# Connector.net
KiCad netlist of a schematic drawn in Altium Designer
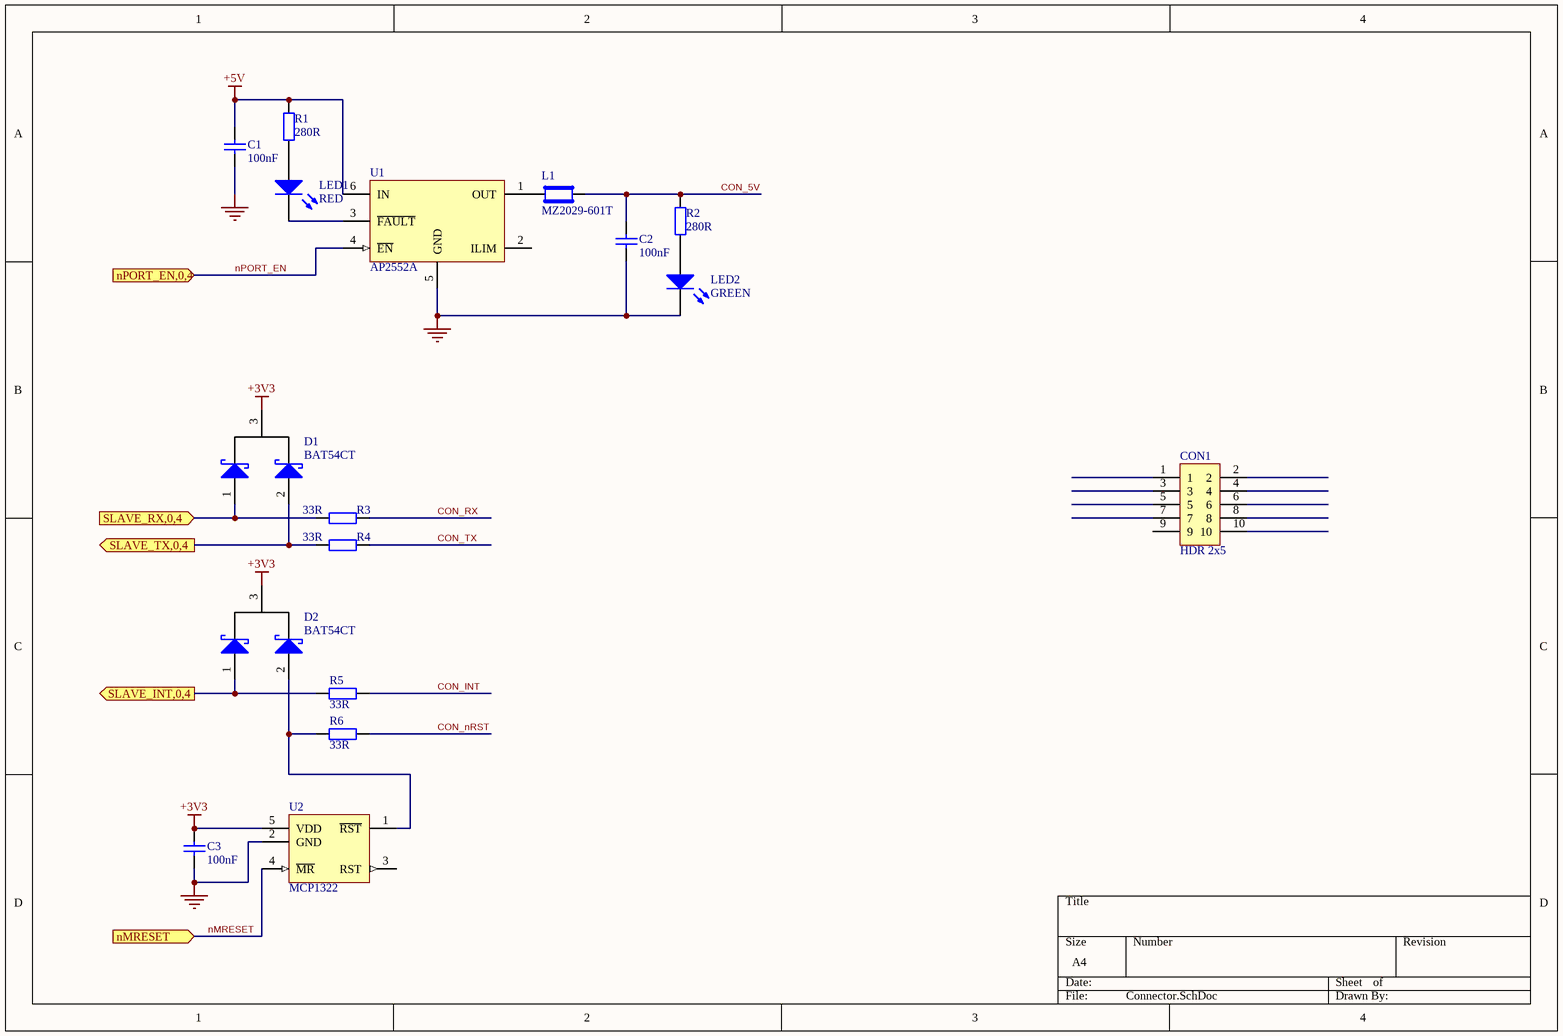
[diagram p0: Connector.SchDoc]

(export (version "E")
  (design (tool "Eeschema 10.0.6"))
  (components
    (comp (ref "C1")
      (value "100nF")
      (footprint "C0805")
      (description "CAP CER 0.1UF 50V 10% X7R 0805")
      (fields (field (name "PART NUMBER") "C0805C104K5RACTU") (field (name "MANUFACTURER") "Kemet"))
      (libsource (lib "AKLib") (part "CAP"))
    )
    (comp (ref "C2")
      (value "100nF")
      (footprint "C0805")
      (description "CAP CER 0.1UF 50V 10% X7R 0805")
      (fields (field (name "PART NUMBER") "C0805C104K5RACTU") (field (name "MANUFACTURER") "Kemet"))
      (libsource (lib "AKLib") (part "CAP"))
    )
    (comp (ref "C3")
      (value "100nF")
      (footprint "C0805")
      (description "CAP CER 0.1UF 50V 10% X7R 0805")
      (fields (field (name "PART NUMBER") "C0805C104K5RACTU") (field (name "MANUFACTURER") "Kemet"))
      (libsource (lib "AKLib") (part "CAP"))
    )
    (comp (ref "CON1")
      (value "HDR 2x5")
      (footprint "SBH11-PBPC-D05-RA-BK")
      (description "CONN HEADR 2.54MM 10POS GOLD R/A")
      (fields
        (field (name "PART NUMBER") "SBH11-PBPC-D05-RA-BK")
        (field (name "MANUFACTURER") "Sullins Connector Solutions")
      )
      (libsource (lib "AKLib") (part "Header 2x5"))
    )
    (comp (ref "D1")
      (value "BAT54CT")
      (footprint "SOT-523")
      (description "DIODE ARRAY SCHOTTKY 30V SOT523")
      (fields (field (name "PART NUMBER") "BAT54CT-7-F") (field (name "MANUFACTURER") "Diodes Incorporated"))
      (libsource (lib "AKLib") (part "Diode-Dual-CC"))
    )
    (comp (ref "D2")
      (value "BAT54CT")
      (footprint "SOT-523")
      (description "DIODE ARRAY SCHOTTKY 30V SOT523")
      (fields (field (name "PART NUMBER") "BAT54CT-7-F") (field (name "MANUFACTURER") "Diodes Incorporated"))
      (libsource (lib "AKLib") (part "Diode-Dual-CC"))
    )
    (comp (ref "L1")
      (value "MZ2029-601T")
      (footprint "L0805")
      (description "FERRITE BEAD 600 OHM 0805 1LN")
      (fields (field (name "MANUFACTURER") "Bourns Inc."))
      (libsource (lib "AKLib") (part "FBEAD"))
    )
    (comp (ref "LED1")
      (value "RED")
      (footprint "Chipled 0805 Red")
      (description "LED RED DIFFUSED 0805 SMD")
      (fields
        (field (name "PART NUMBER") "LH R974-LP-1")
        (field (name "MANUFACTURER") "OSRAM Opto Semiconductors Inc.")
      )
      (libsource (lib "AKLib") (part "LED"))
    )
    (comp (ref "LED2")
      (value "GREEN")
      (footprint "Chipled 0805 Green")
      (description "LED GREEN DIFFUSED 0805 SMD")
      (fields
        (field (name "PART NUMBER") "LG R971-KN-1")
        (field (name "MANUFACTURER") "OSRAM Opto Semiconductors Inc.")
      )
      (libsource (lib "AKLib") (part "LED"))
    )
    (comp (ref "R1")
      (value "280R")
      (footprint "R0805")
      (description "RES SMD 280 OHM 1% 1/8W 0805")
      (fields (field (name "PART NUMBER") "RC0805FR-07280RL") (field (name "MANUFACTURER") "Yageo"))
      (libsource (lib "AKLib") (part "RES"))
    )
    (comp (ref "R2")
      (value "280R")
      (footprint "R0805")
      (description "RES SMD 280 OHM 1% 1/8W 0805")
      (fields (field (name "PART NUMBER") "RC0805FR-07280RL") (field (name "MANUFACTURER") "Yageo"))
      (libsource (lib "AKLib") (part "RES"))
    )
    (comp (ref "R3")
      (value "33R")
      (footprint "R0805")
      (description "RES SMD 33 OHM 5% 1/8W 0805")
      (fields (field (name "PART NUMBER") "RC0805JR-0733RL") (field (name "MANUFACTURER") "Yageo"))
      (libsource (lib "") (part "RES_1"))
    )
    (comp (ref "R4")
      (value "33R")
      (footprint "R0805")
      (description "RES SMD 33 OHM 5% 1/8W 0805")
      (fields (field (name "PART NUMBER") "RC0805JR-0733RL") (field (name "MANUFACTURER") "Yageo"))
      (libsource (lib "") (part "RES_1"))
    )
    (comp (ref "R5")
      (value "33R")
      (footprint "R0805")
      (description "RES SMD 33 OHM 5% 1/8W 0805")
      (fields (field (name "PART NUMBER") "RC0805JR-0733RL") (field (name "MANUFACTURER") "Yageo"))
      (libsource (lib "") (part "RES_1"))
    )
    (comp (ref "R6")
      (value "33R")
      (footprint "R0805")
      (description "RES SMD 33 OHM 5% 1/8W 0805")
      (fields (field (name "PART NUMBER") "RC0805JR-0733RL") (field (name "MANUFACTURER") "Yageo"))
      (libsource (lib "") (part "RES_1"))
    )
    (comp (ref "U1")
      (value "AP2552A")
      (footprint "SOT26")
      (description "IC PD SW CURR LIMIT SOT26")
      (fields (field (name "PART NUMBER") "AP2552AW6-7") (field (name "MANUFACTURER") "Diodes Incorporated"))
      (libsource (lib "AKLib") (part "AP255xA"))
    )
    (comp (ref "U2")
      (value "MCP1322")
      (footprint "SOT23-5")
      (description "IC SUPERVISOR 4.6V SOT23-5")
      (fields
        (field (name "PART NUMBER") "MCP1322T-46LE/OT")
        (field (name "MANUFACTURER") "Microchip Technology")
      )
      (libsource (lib "AKLib") (part "MCP1322"))
    )
  )
  (nets
    (net (code "1") (name "+3V3") (class "Default")
      (node (ref "C3") (pin "2") (pinfunction "2_2") (pintype "passive"))
      (node (ref "D1") (pin "3") (pinfunction "A_3") (pintype "passive"))
      (node (ref "D2") (pin "3") (pinfunction "A_3") (pintype "passive"))
      (node (ref "U2") (pin "5") (pinfunction "VDD_5") (pintype "power_in"))
    )
    (net (code "2") (name "+5V") (class "Default")
      (node (ref "C1") (pin "2") (pinfunction "2_2") (pintype "passive"))
      (node (ref "R1") (pin "2") (pinfunction "2_2") (pintype "passive"))
      (node (ref "U1") (pin "6") (pinfunction "IN_6") (pintype "power_in"))
    )
    (net (code "3") (name "/CON_5V") (class "Default")
      (node (ref "C2") (pin "2") (pinfunction "2_2") (pintype "passive"))
      (node (ref "L1") (pin "2") (pinfunction "2_2") (pintype "passive"))
      (node (ref "R2") (pin "2") (pinfunction "2_2") (pintype "passive"))
    )
    (net (code "4") (name "/CON_INT") (class "Default")
      (node (ref "R5") (pin "2") (pinfunction "2_2") (pintype "passive"))
    )
    (net (code "5") (name "/CON_RX") (class "Default")
      (node (ref "R3") (pin "2") (pinfunction "2_2") (pintype "passive"))
    )
    (net (code "6") (name "/CON_TX") (class "Default")
      (node (ref "R4") (pin "2") (pinfunction "2_2") (pintype "passive"))
    )
    (net (code "7") (name "/CON_nRST") (class "Default")
      (node (ref "R6") (pin "2") (pinfunction "2_2") (pintype "passive"))
    )
    (net (code "8") (name "/SLAVE_INT,0,4") (class "Default")
      (node (ref "D2") (pin "1") (pinfunction "K_1") (pintype "passive"))
      (node (ref "R5") (pin "1") (pinfunction "1_1") (pintype "passive"))
    )
    (net (code "9") (name "/SLAVE_RX,0,4") (class "Default")
      (node (ref "D1") (pin "1") (pinfunction "K_1") (pintype "passive"))
      (node (ref "R3") (pin "1") (pinfunction "1_1") (pintype "passive"))
    )
    (net (code "10") (name "/SLAVE_TX,0,4") (class "Default")
      (node (ref "D1") (pin "2") (pinfunction "K_2") (pintype "passive"))
      (node (ref "R4") (pin "1") (pinfunction "1_1") (pintype "passive"))
    )
    (net (code "11") (name "/nMRESET") (class "Default")
      (node (ref "U2") (pin "4") (pinfunction "~{MR}_4") (pintype "input"))
    )
    (net (code "12") (name "/nPORT_EN") (class "Default")
      (node (ref "U1") (pin "4") (pinfunction "~{EN}_4") (pintype "input"))
    )
    (net (code "13") (name "GND") (class "Default")
      (node (ref "C1") (pin "1") (pinfunction "1_1") (pintype "passive"))
      (node (ref "C2") (pin "1") (pinfunction "1_1") (pintype "passive"))
      (node (ref "C3") (pin "1") (pinfunction "1_1") (pintype "passive"))
      (node (ref "LED2") (pin "2") (pinfunction "K_2") (pintype "passive"))
      (node (ref "U1") (pin "5") (pinfunction "GND_5") (pintype "power_in"))
      (node (ref "U2") (pin "2") (pinfunction "GND_2") (pintype "power_in"))
    )
    (net (code "14") (name "Net-(LED1-A)") (class "Default")
      (node (ref "LED1") (pin "1") (pinfunction "A_1") (pintype "passive"))
      (node (ref "R1") (pin "1") (pinfunction "1_1") (pintype "passive"))
    )
    (net (code "15") (name "Net-(LED1-K)") (class "Default")
      (node (ref "LED1") (pin "2") (pinfunction "K_2") (pintype "passive"))
      (node (ref "U1") (pin "3") (pinfunction "~{FAULT}_3") (pintype "open_collector"))
    )
    (net (code "16") (name "Net-(LED2-A)") (class "Default")
      (node (ref "LED2") (pin "1") (pinfunction "A_1") (pintype "passive"))
      (node (ref "R2") (pin "1") (pinfunction "1_1") (pintype "passive"))
    )
    (net (code "17") (name "Net-(U1-OUT)") (class "Default")
      (node (ref "L1") (pin "1") (pinfunction "1_1") (pintype "passive"))
      (node (ref "U1") (pin "1") (pinfunction "OUT_1") (pintype "power_in"))
    )
    (net (code "18") (name "Net-(U2-~{RST})") (class "Default")
      (node (ref "D2") (pin "2") (pinfunction "K_2") (pintype "passive"))
      (node (ref "R6") (pin "1") (pinfunction "1_1") (pintype "passive"))
      (node (ref "U2") (pin "1") (pinfunction "~{RST}_1") (pintype "open_collector"))
    )
    (net (code "19") (name "unconnected-(CON1-Pad1)") (class "Default")
      (node (ref "CON1") (pin "1") (pinfunction "1_1") (pintype "passive"))
    )
    (net (code "20") (name "unconnected-(CON1-Pad2)") (class "Default")
      (node (ref "CON1") (pin "2") (pinfunction "2_2") (pintype "passive"))
    )
    (net (code "21") (name "unconnected-(CON1-Pad3)") (class "Default")
      (node (ref "CON1") (pin "3") (pinfunction "3_3") (pintype "passive"))
    )
    (net (code "22") (name "unconnected-(CON1-Pad4)") (class "Default")
      (node (ref "CON1") (pin "4") (pinfunction "4_4") (pintype "passive"))
    )
    (net (code "23") (name "unconnected-(CON1-Pad5)") (class "Default")
      (node (ref "CON1") (pin "5") (pinfunction "5_5") (pintype "passive"))
    )
    (net (code "24") (name "unconnected-(CON1-Pad6)") (class "Default")
      (node (ref "CON1") (pin "6") (pinfunction "6_6") (pintype "passive"))
    )
    (net (code "25") (name "unconnected-(CON1-Pad7)") (class "Default")
      (node (ref "CON1") (pin "7") (pinfunction "7_7") (pintype "passive"))
    )
    (net (code "26") (name "unconnected-(CON1-Pad8)") (class "Default")
      (node (ref "CON1") (pin "8") (pinfunction "8_8") (pintype "passive"))
    )
    (net (code "27") (name "unconnected-(CON1-Pad9)") (class "Default")
      (node (ref "CON1") (pin "9") (pinfunction "9_9") (pintype "passive"))
    )
    (net (code "28") (name "unconnected-(CON1-Pad10)") (class "Default")
      (node (ref "CON1") (pin "10") (pinfunction "10_10") (pintype "passive"))
    )
    (net (code "29") (name "unconnected-(U1-ILIM-Pad2)") (class "Default")
      (node (ref "U1") (pin "2") (pinfunction "ILIM_2") (pintype "passive"))
    )
    (net (code "30") (name "unconnected-(U2-RST-Pad3)") (class "Default")
      (node (ref "U2") (pin "3") (pinfunction "RST_3") (pintype "output"))
    )
  )
)
